# LiPoBattery.net
KiCad netlist of a schematic drawn in Altium Designer
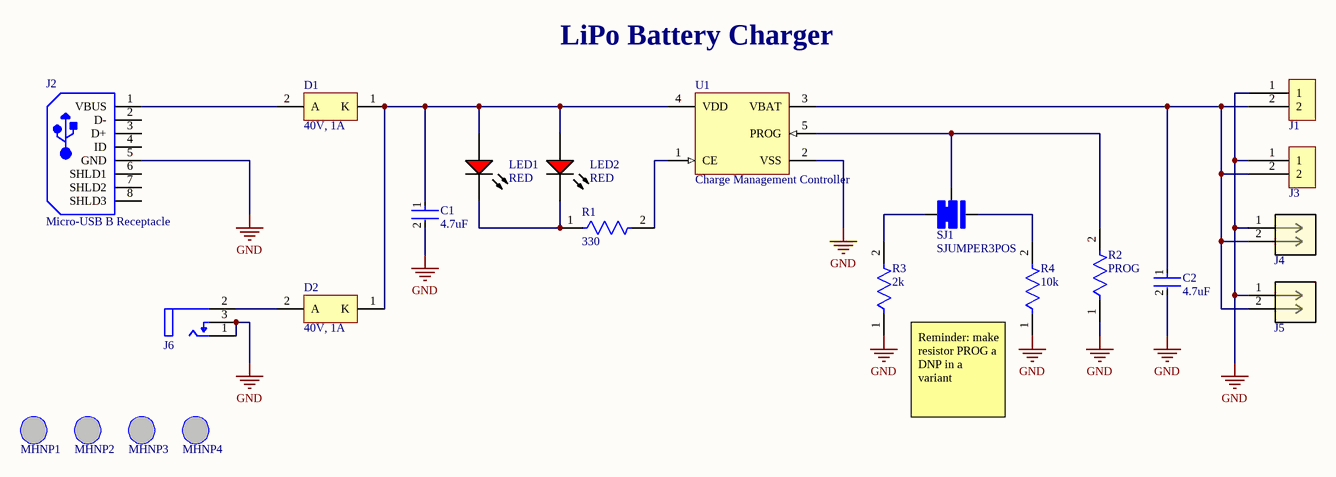
[diagram p0: LiPoBattery.SchDoc]

(export (version "E")
  (design (tool "Eeschema 10.0.6"))
  (components
    (comp (ref "C1")
      (value "4.7uF")
      (footprint "FP-CC0805-0_85-MFG")
      (description "CAP CER 4.7UF 6.3V X7R 0805")
      (fields (field (name "MANUFACTURER") "Yageo") (field (name "TOLERANCE") "0.1"))
      (libsource (lib "Altium Content Vault") (part "11868f565c42a9108669ba33697ecf6"))
    )
    (comp (ref "C2")
      (value "4.7uF")
      (footprint "FP-CC0805-0_85-MFG")
      (description "CAP CER 4.7UF 6.3V X7R 0805")
      (fields (field (name "MANUFACTURER") "Yageo") (field (name "TOLERANCE") "0.1"))
      (libsource (lib "Altium Content Vault") (part "11868f565c42a9108669ba33697ecf6"))
    )
    (comp (ref "D1")
      (value "40V, 1A")
      (footprint "ONSC-SMA-2-403D-02_V")
      (description "Schottky Power Rectifier, 2-Pin SMA, Pb-Free, Tape and Reel")
      (fields (field (name "PARTNUMBER") "MBRA140T3G") (field (name "MANUFACTURER") "On Semiconductor"))
      (libsource (lib "Altium Content Vault") (part "ONSC-D-K1A2-2_A"))
    )
    (comp (ref "D2")
      (value "40V, 1A")
      (footprint "ONSC-SMA-2-403D-02_V")
      (description "Schottky Power Rectifier, 2-Pin SMA, Pb-Free, Tape and Reel")
      (fields (field (name "PARTNUMBER") "MBRA140T3G") (field (name "MANUFACTURER") "On Semiconductor"))
      (libsource (lib "Altium Content Vault") (part "ONSC-D-K1A2-2_A"))
    )
    (comp (ref "J1")
      (value "CONN HEADER R/A 2POS 5.08MM")
      (footprint "1-179276-2")
      (description "Connector Header Through Hole, Right Angle 2 position 0.200\" (5.08mm)")
      (fields
        (field (name "MANUFACTURER") "TE Connectivity AMP Connectors")
        (field (name "MANUFACTURER PART NUMBER") "1-179276-2")
      )
      (libsource (lib "LiPoBattery") (part "1-179276-2"))
    )
    (comp (ref "J2")
      (value "Micro-USB B Receptacle")
      (footprint "MOLX-105133-0001_V")
      (description "Micro-USB B Receptacle, Vertical, -30 to 85 degC, 5-Pin SMD, RoHS, Tape and Reel")
      (fields (field (name "MANUFACTURER") "Molex") (field (name "PARTNUMBER") "105133-0001"))
      (libsource (lib "Altium Content Vault") (part "USB-5-3SHLD"))
    )
    (comp (ref "J3")
      (value "CONN HEADER R/A 2POS 5.08MM")
      (footprint "1-179276-2")
      (description "Connector Header Through Hole, Right Angle 2 position 0.200\" (5.08mm)")
      (fields
        (field (name "MANUFACTURER") "TE Connectivity AMP Connectors")
        (field (name "MANUFACTURER PART NUMBER") "1-179276-2")
      )
      (libsource (lib "LiPoBattery") (part "1-179276-2"))
    )
    (comp (ref "J4")
      (value "2 POS VERT HEADER 0.100'")
      (footprint "2Pins_AMP")
      (description "Connector Header Through Hole 2 position")
      (fields
        (field (name "MANUFACTURER_PART_NUMBER") "67997-402HLF")
        (field (name "COPYRIGHT") "Copyright (C) 2025 Ultra Librarian. All rights reserved.")
      )
      (libsource (lib "LiPoBattery") (part "67997-402HLF"))
    )
    (comp (ref "J5")
      (value "2 POS VERT HEADER 0.100'")
      (footprint "2Pins_AMP")
      (description "Connector Header Through Hole 2 position")
      (fields
        (field (name "MANUFACTURER_PART_NUMBER") "67997-402HLF")
        (field (name "COPYRIGHT") "Copyright (C) 2025 Ultra Librarian. All rights reserved.")
      )
      (libsource (lib "LiPoBattery") (part "67997-402HLF"))
    )
    (comp (ref "J6")
      (value "CONN PWR JACK 2.1X5.5MM SOLDER")
      (footprint "FP-RASM722PTR13X-MFG")
      (libsource (lib "Altium Content Vault") (part "69023cd999ddc70d2a190894d9bbb58"))
    )
    (comp (ref "LED1")
      (value "RED")
      (footprint "VISH-TLMS1000_V")
      (description "Low Current LED, 40 mW, 1.8 V, -40 to 100 degC, 2-Pin SMD (0603), RoHS, Tape and Reel")
      (fields (field (name "MANUFACTURER") "Vishay"))
      (libsource (lib "Altium Content Vault") (part "LED-RED-AK-2"))
    )
    (comp (ref "LED2")
      (value "RED")
      (footprint "VISH-TLMS1000_V")
      (description "Low Current LED, 40 mW, 1.8 V, -40 to 100 degC, 2-Pin SMD (0603), RoHS, Tape and Reel")
      (fields (field (name "MANUFACTURER") "Vishay"))
      (libsource (lib "Altium Content Vault") (part "LED-RED-AK-2"))
    )
    (comp (ref "MHNP1")
      (value "Mounting Hole Non-Plated 3.2mm")
      (footprint "MTHNP3P2MM")
      (description "Mounting Hole Non-Plated 3.2mm drill hole")
      (libsource (lib "LiPoBattery") (part "MTHNP3P2MM"))
    )
    (comp (ref "MHNP2")
      (value "Mounting Hole Non-Plated 3.2mm")
      (footprint "MTHNP3P2MM")
      (description "Mounting Hole Non-Plated 3.2mm drill hole")
      (libsource (lib "LiPoBattery") (part "MTHNP3P2MM"))
    )
    (comp (ref "MHNP3")
      (value "Mounting Hole Non-Plated 3.2mm")
      (footprint "MTHNP3P2MM")
      (description "Mounting Hole Non-Plated 3.2mm drill hole")
      (libsource (lib "LiPoBattery") (part "MTHNP3P2MM"))
    )
    (comp (ref "MHNP4")
      (value "Mounting Hole Non-Plated 3.2mm")
      (footprint "MTHNP3P2MM")
      (description "Mounting Hole Non-Plated 3.2mm drill hole")
      (libsource (lib "LiPoBattery") (part "MTHNP3P2MM"))
    )
    (comp (ref "R1")
      (value "330")
      (footprint "FP-CRCW0805-e3-IPC_C")
      (description "RES Thick Film, 330Ω, 5%, 0.125W, 200ppm/°C, 0805")
      (fields (field (name "TOLERANCE") "5%"))
      (libsource (lib "Altium Content Vault") (part "1029c3af85768c4190bb7ad29bc67b5"))
    )
    (comp (ref "R2")
      (value "PROG")
      (footprint "FP-RS02B-MFG")
      (description "Res Wirewound 12K Ohm 1% 3W ±20ppm/°C Ceramic Hi Temp Sil AXL Thru-Hole Bulk")
      (fields (field (name "TOLERANCE") "1%"))
      (libsource (lib "Altium Content Vault") (part "1029c3af85768c4190bb7ad29bc67b5"))
    )
    (comp (ref "R3")
      (value "2k")
      (footprint "FP-RN73R2A-IPC_B")
      (description "2kΩ ±0.5% 0.125W, 1/8W Chip Resistor 0805 (2012 Metric) Moisture Resistant Thin Film")
      (libsource (lib "Altium Content Vault") (part "1029c3af85768c4190bb7ad29bc67b5"))
    )
    (comp (ref "R4")
      (value "10k")
      (footprint "FP-CRGP0805-IPC_C")
      (description "CRGP 0805 10K 1%")
      (fields (field (name "MANUFACTURER PART NUMBER") "CRGP0805F10K") (field (name "MANUFACTURER") "TE"))
      (libsource (lib "Altium Content Vault") (part "1029c3af85768c4190bb7ad29bc67b5"))
    )
    (comp (ref "SJ1")
      (value "SJUMPER3POS")
      (footprint "SJUMPER3POS-Footprint-1")
      (description "Solder jumper 3 pads and pins")
      (libsource (lib "Personal Projects") (part "SJUMPER3POS"))
    )
    (comp (ref "U1")
      (value "Charge Management Controller")
      (footprint "SOT-23-OT5_M")
      (libsource (lib "Altium Content Vault") (part "PM-BM-MCP7381X-SOT5"))
    )
  )
  (nets
    (net (code "1") (name "GND") (class "Default")
      (node (ref "C1") (pin "2") (pinfunction "2_2") (pintype "passive"))
      (node (ref "C2") (pin "2") (pinfunction "2_2") (pintype "passive"))
      (node (ref "J1") (pin "1") (pinfunction "1_1") (pintype "passive"))
      (node (ref "J2") (pin "5") (pinfunction "GND_5") (pintype "passive"))
      (node (ref "J3") (pin "1") (pinfunction "1_1") (pintype "passive"))
      (node (ref "J4") (pin "1") (pinfunction "1_1") (pintype "passive"))
      (node (ref "J5") (pin "1") (pinfunction "1_1") (pintype "passive"))
      (node (ref "J6") (pin "1") (pinfunction "TIP_TERMINAL(CENTER_PIN)_1") (pintype "passive"))
      (node (ref "J6") (pin "3") (pinfunction "SHUNT_TERMINAL_3") (pintype "passive"))
      (node (ref "R2") (pin "1") (pinfunction "1_1") (pintype "passive"))
      (node (ref "R3") (pin "1") (pinfunction "1_1") (pintype "passive"))
      (node (ref "R4") (pin "1") (pinfunction "1_1") (pintype "passive"))
      (node (ref "U1") (pin "2") (pinfunction "VSS_2") (pintype "power_in"))
    )
    (net (code "2") (name "Net-(D1-A)") (class "Default")
      (node (ref "D1") (pin "2") (pinfunction "A_2") (pintype "passive"))
      (node (ref "J2") (pin "1") (pinfunction "VBUS_1") (pintype "passive"))
    )
    (net (code "3") (name "Net-(D1-K)") (class "Default")
      (node (ref "C1") (pin "1") (pinfunction "1_1") (pintype "passive"))
      (node (ref "D1") (pin "1") (pinfunction "K_1") (pintype "passive"))
      (node (ref "D2") (pin "1") (pinfunction "K_1") (pintype "passive"))
      (node (ref "LED1") (pin "1") (pinfunction "A_1") (pintype "passive"))
      (node (ref "LED2") (pin "1") (pinfunction "A_1") (pintype "passive"))
      (node (ref "U1") (pin "4") (pinfunction "VDD_4") (pintype "power_in"))
    )
    (net (code "4") (name "Net-(D2-A)") (class "Default")
      (node (ref "D2") (pin "2") (pinfunction "A_2") (pintype "passive"))
      (node (ref "J6") (pin "2") (pinfunction "SLEEVE_TERMINAL_2") (pintype "passive"))
    )
    (net (code "5") (name "Net-(LED1-K)") (class "Default")
      (node (ref "LED1") (pin "2") (pinfunction "K_2") (pintype "passive"))
      (node (ref "LED2") (pin "2") (pinfunction "K_2") (pintype "passive"))
      (node (ref "R1") (pin "1") (pinfunction "1_1") (pintype "passive"))
    )
    (net (code "6") (name "Net-(R3-Pad2)") (class "Default")
      (node (ref "R3") (pin "2") (pinfunction "2_2") (pintype "passive"))
      (node (ref "SJ1") (pin "1") (pinfunction "1_1") (pintype "passive"))
    )
    (net (code "7") (name "Net-(R4-Pad2)") (class "Default")
      (node (ref "R4") (pin "2") (pinfunction "2_2") (pintype "passive"))
      (node (ref "SJ1") (pin "3") (pinfunction "3_3") (pintype "passive"))
    )
    (net (code "8") (name "Net-(U1-CE)") (class "Default")
      (node (ref "R1") (pin "2") (pinfunction "2_2") (pintype "passive"))
      (node (ref "U1") (pin "1") (pinfunction "CE_1") (pintype "input"))
    )
    (net (code "9") (name "Net-(U1-PROG)") (class "Default")
      (node (ref "R2") (pin "2") (pinfunction "2_2") (pintype "passive"))
      (node (ref "SJ1") (pin "2") (pinfunction "2_2") (pintype "passive"))
      (node (ref "U1") (pin "5") (pinfunction "PROG_5") (pintype "input"))
    )
    (net (code "10") (name "Net-(U1-VBAT)") (class "Default")
      (node (ref "C2") (pin "1") (pinfunction "1_1") (pintype "passive"))
      (node (ref "J1") (pin "2") (pinfunction "2_2") (pintype "passive"))
      (node (ref "J3") (pin "2") (pinfunction "2_2") (pintype "passive"))
      (node (ref "J4") (pin "2") (pinfunction "2_2") (pintype "passive"))
      (node (ref "J5") (pin "2") (pinfunction "2_2") (pintype "passive"))
      (node (ref "U1") (pin "3") (pinfunction "VBAT_3") (pintype "power_in"))
    )
    (net (code "11") (name "unconnected-(J2-D+-Pad3)") (class "Default")
      (node (ref "J2") (pin "3") (pinfunction "D+_3") (pintype "passive"))
    )
    (net (code "12") (name "unconnected-(J2-D--Pad2)") (class "Default")
      (node (ref "J2") (pin "2") (pinfunction "D-_2") (pintype "passive"))
    )
    (net (code "13") (name "unconnected-(J2-ID-Pad4)") (class "Default")
      (node (ref "J2") (pin "4") (pinfunction "ID_4") (pintype "passive"))
    )
    (net (code "14") (name "unconnected-(J2-SHLD1-Pad6)") (class "Default")
      (node (ref "J2") (pin "6") (pinfunction "SHLD1_6") (pintype "passive"))
    )
    (net (code "15") (name "unconnected-(J2-SHLD2-Pad7)") (class "Default")
      (node (ref "J2") (pin "7") (pinfunction "SHLD2_7") (pintype "passive"))
    )
    (net (code "16") (name "unconnected-(J2-SHLD3-Pad8)") (class "Default")
      (node (ref "J2") (pin "8") (pinfunction "SHLD3_8") (pintype "passive"))
    )
  )
)
